# LT1013.net
KiCad netlist of a schematic drawn in EAGLE
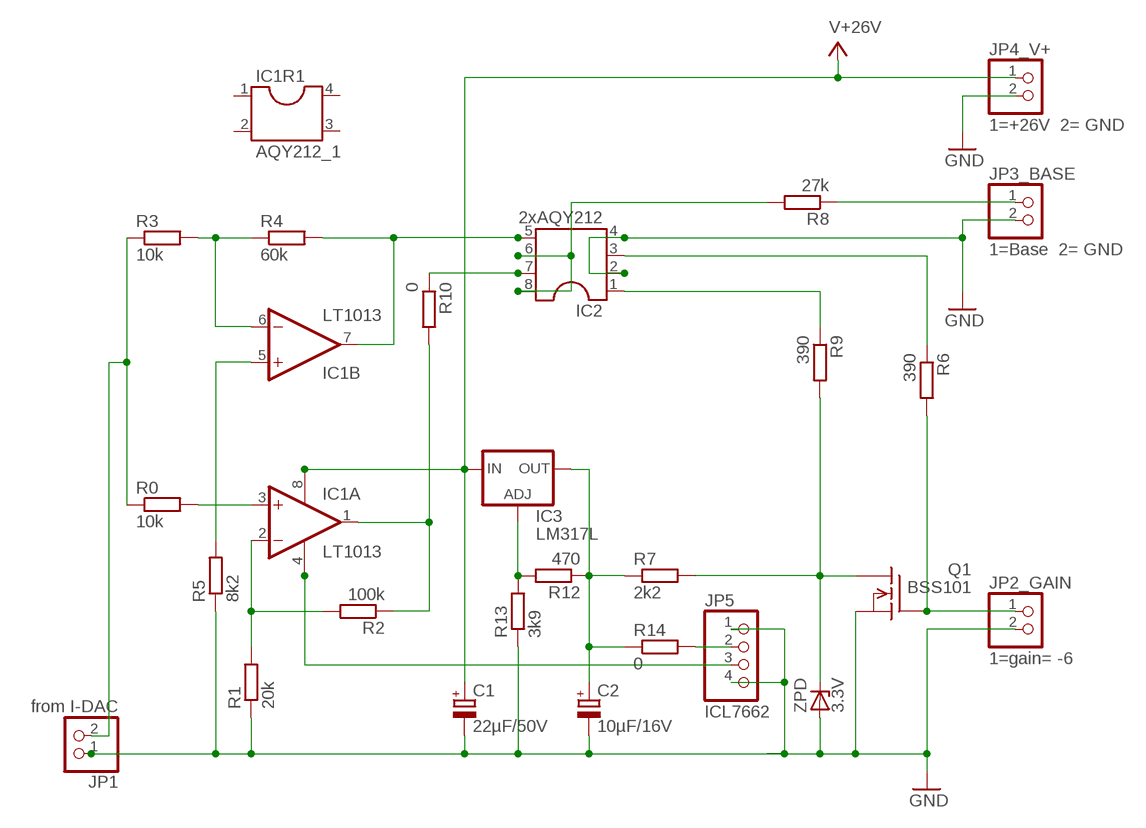
[diagram p0: schematic, sheet 1]

(export (version "E")
  (design (tool "Eeschema 10.0.6"))
  (components
    (comp (ref "C1")
      (value "22µF/50V")
      (footprint "eagle-import:E5-10,5")
      (libsource (lib "eagle-import") (part "CPOL-EUE5-10.5"))
    )
    (comp (ref "C2")
      (value "10µF/16V")
      (footprint "eagle-import:B45181B")
      (libsource (lib "eagle-import") (part "resistor_348_CPOL-EUB45181B"))
    )
    (comp (ref "IC1")
      (value "LT1013")
      (footprint "eagle-import:DIL08")
      (libsource (lib "eagle-import") (part "LF412N"))
    )
    (comp (ref "IC1R1")
      (value "AQY212_1")
      (footprint "eagle-import:SOCKET-04")
      (libsource (lib "eagle-import") (part "DIL4S"))
    )
    (comp (ref "IC2")
      (value "2xAQY212")
      (footprint "eagle-import:SOCKET-08")
      (libsource (lib "eagle-import") (part "DIL8S"))
    )
    (comp (ref "IC3")
      (value "LM317L")
      (footprint "eagle-import:317L")
      (libsource (lib "eagle-import") (part "LM317L"))
    )
    (comp (ref "JP1")
      (value "from I-DAC")
      (footprint "eagle-import:1X02")
      (libsource (lib "eagle-import") (part "PINHD-1X2"))
    )
    (comp (ref "JP2_GAIN")
      (value "1=gain= -6")
      (footprint "eagle-import:1X02")
      (libsource (lib "eagle-import") (part "PINHD-1X2"))
    )
    (comp (ref "JP3_BASE")
      (value "1=Base 2= GND")
      (footprint "eagle-import:1X02")
      (libsource (lib "eagle-import") (part "PINHD-1X2"))
    )
    (comp (ref "JP4_V+")
      (value "1=+26V 2= GND")
      (footprint "eagle-import:1X02")
      (libsource (lib "eagle-import") (part "PINHD-1X2"))
    )
    (comp (ref "JP5")
      (value "ICL7662")
      (footprint "eagle-import:1X04")
      (libsource (lib "eagle-import") (part "PINHD-1X4"))
    )
    (comp (ref "Q1")
      (value "BSS101")
      (footprint "eagle-import:TO92")
      (libsource (lib "eagle-import") (part "BSS101"))
    )
    (comp (ref "R0")
      (value "10k")
      (footprint "eagle-import:0207_7")
      (libsource (lib "eagle-import") (part "R-EU_0207/7"))
    )
    (comp (ref "R1")
      (value "20k")
      (footprint "eagle-import:0207_7")
      (libsource (lib "eagle-import") (part "R-EU_0207/7"))
    )
    (comp (ref "R2")
      (value "100k")
      (footprint "eagle-import:0207_7")
      (libsource (lib "eagle-import") (part "R-EU_0207/7"))
    )
    (comp (ref "R3")
      (value "10k")
      (footprint "eagle-import:0207_7")
      (libsource (lib "eagle-import") (part "R-EU_0207/7"))
    )
    (comp (ref "R4")
      (value "60k")
      (footprint "eagle-import:0207_7")
      (libsource (lib "eagle-import") (part "R-EU_0207/7"))
    )
    (comp (ref "R5")
      (value "8k2")
      (footprint "eagle-import:0207_7")
      (libsource (lib "eagle-import") (part "R-EU_0207/7"))
    )
    (comp (ref "R6")
      (value "390")
      (footprint "eagle-import:0207_7")
      (libsource (lib "eagle-import") (part "R-EU_0207/7"))
    )
    (comp (ref "R7")
      (value "2k2")
      (footprint "eagle-import:0207_7")
      (libsource (lib "eagle-import") (part "R-EU_0207/7"))
    )
    (comp (ref "R8")
      (value "27k")
      (footprint "eagle-import:0207_7")
      (libsource (lib "eagle-import") (part "R-EU_0207/7"))
    )
    (comp (ref "R9")
      (value "390")
      (footprint "eagle-import:0207_7")
      (libsource (lib "eagle-import") (part "R-EU_0207/7"))
    )
    (comp (ref "R10")
      (value "0")
      (footprint "eagle-import:0207_7")
      (libsource (lib "eagle-import") (part "R-EU_0207/7"))
    )
    (comp (ref "R12")
      (value "470")
      (footprint "eagle-import:0207_7")
      (libsource (lib "eagle-import") (part "R-EU_0207/7"))
    )
    (comp (ref "R13")
      (value "3k9")
      (footprint "eagle-import:0207_7")
      (libsource (lib "eagle-import") (part "R-EU_0207/7"))
    )
    (comp (ref "R14")
      (value "0")
      (footprint "eagle-import:0207_7")
      (libsource (lib "eagle-import") (part "R-EU_0207/7"))
    )
    (comp (ref "ZPD")
      (value "3.3V")
      (footprint "eagle-import:ZDIO-7.5")
      (libsource (lib "eagle-import") (part "ZENER-DIODEZD-7.5"))
    )
  )
  (nets
    (net (code "1") (name "GND") (class "Default")
      (node (ref "C1") (pin "-") (pinfunction "-_-") (pintype "passive"))
      (node (ref "C2") (pin "-") (pinfunction "-_-") (pintype "passive"))
      (node (ref "IC2") (pin "2") (pinfunction "2_2") (pintype "passive"))
      (node (ref "IC2") (pin "4") (pinfunction "4_4") (pintype "passive"))
      (node (ref "JP1") (pin "1") (pinfunction "1_1") (pintype "passive"))
      (node (ref "JP2_GAIN") (pin "2") (pinfunction "2_2") (pintype "passive"))
      (node (ref "JP3_BASE") (pin "2") (pinfunction "2_2") (pintype "passive"))
      (node (ref "JP4_V+") (pin "2") (pinfunction "2_2") (pintype "passive"))
      (node (ref "JP5") (pin "1") (pinfunction "1_1") (pintype "passive"))
      (node (ref "JP5") (pin "4") (pinfunction "4_4") (pintype "passive"))
      (node (ref "Q1") (pin "1") (pinfunction "S_1") (pintype "passive"))
      (node (ref "R1") (pin "1") (pinfunction "1_1") (pintype "passive"))
      (node (ref "R13") (pin "1") (pinfunction "1_1") (pintype "passive"))
      (node (ref "R5") (pin "1") (pinfunction "1_1") (pintype "passive"))
      (node (ref "ZPD") (pin "A") (pinfunction "A_A") (pintype "passive"))
    )
    (net (code "2") (name "Net-(IC1A-+IN)") (class "Default")
      (node (ref "IC1") (pin "3") (pinfunction "+IN_3") (pintype "input"))
      (node (ref "R0") (pin "2") (pinfunction "2_2") (pintype "passive"))
    )
    (net (code "3") (name "Net-(IC1A--IN)") (class "Default")
      (node (ref "IC1") (pin "2") (pinfunction "-IN_2") (pintype "input"))
      (node (ref "R1") (pin "2") (pinfunction "2_2") (pintype "passive"))
      (node (ref "R2") (pin "2") (pinfunction "2_2") (pintype "passive"))
    )
    (net (code "4") (name "Net-(IC1A-OUT)") (class "Default")
      (node (ref "IC1") (pin "1") (pinfunction "OUT_1") (pintype "output"))
      (node (ref "R10") (pin "2") (pinfunction "2_2") (pintype "passive"))
      (node (ref "R2") (pin "1") (pinfunction "1_1") (pintype "passive"))
    )
    (net (code "5") (name "Net-(IC1B-+IN)") (class "Default")
      (node (ref "IC1") (pin "5") (pinfunction "+IN_5") (pintype "input"))
      (node (ref "R5") (pin "2") (pinfunction "2_2") (pintype "passive"))
    )
    (net (code "6") (name "Net-(IC1B--IN)") (class "Default")
      (node (ref "IC1") (pin "6") (pinfunction "-IN_6") (pintype "input"))
      (node (ref "R3") (pin "2") (pinfunction "2_2") (pintype "passive"))
      (node (ref "R4") (pin "1") (pinfunction "1_1") (pintype "passive"))
    )
    (net (code "7") (name "Net-(IC1B-OUT)") (class "Default")
      (node (ref "IC1") (pin "7") (pinfunction "OUT_7") (pintype "output"))
      (node (ref "IC2") (pin "5") (pinfunction "5_5") (pintype "passive"))
      (node (ref "R4") (pin "2") (pinfunction "2_2") (pintype "passive"))
    )
    (net (code "8") (name "Net-(IC1C-V-)") (class "Default")
      (node (ref "IC1") (pin "4") (pinfunction "V-_4") (pintype "power_in"))
      (node (ref "JP5") (pin "3") (pinfunction "3_3") (pintype "passive"))
    )
    (net (code "9") (name "Net-(IC2-Pad1)") (class "Default")
      (node (ref "IC2") (pin "1") (pinfunction "1_1") (pintype "passive"))
      (node (ref "R9") (pin "1") (pinfunction "1_1") (pintype "passive"))
    )
    (net (code "10") (name "Net-(IC2-Pad3)") (class "Default")
      (node (ref "IC2") (pin "3") (pinfunction "3_3") (pintype "passive"))
      (node (ref "R6") (pin "1") (pinfunction "1_1") (pintype "passive"))
    )
    (net (code "11") (name "Net-(IC2-Pad6)") (class "Default")
      (node (ref "IC2") (pin "6") (pinfunction "6_6") (pintype "passive"))
      (node (ref "IC2") (pin "8") (pinfunction "8_8") (pintype "passive"))
      (node (ref "R8") (pin "2") (pinfunction "2_2") (pintype "passive"))
    )
    (net (code "12") (name "Net-(IC2-Pad7)") (class "Default")
      (node (ref "IC2") (pin "7") (pinfunction "7_7") (pintype "passive"))
      (node (ref "R10") (pin "1") (pinfunction "1_1") (pintype "passive"))
    )
    (net (code "13") (name "Net-(IC3-ADJ)") (class "Default")
      (node (ref "IC3") (pin "1") (pinfunction "ADJ_1") (pintype "input"))
      (node (ref "R12") (pin "2") (pinfunction "2_2") (pintype "passive"))
      (node (ref "R13") (pin "2") (pinfunction "2_2") (pintype "passive"))
    )
    (net (code "14") (name "Net-(IC3-OUT)") (class "Default")
      (node (ref "C2") (pin "+") (pinfunction "+_+") (pintype "passive"))
      (node (ref "IC3") (pin "2") (pinfunction "OUT_2") (pintype "passive"))
      (node (ref "R12") (pin "1") (pinfunction "1_1") (pintype "passive"))
      (node (ref "R14") (pin "1") (pinfunction "1_1") (pintype "passive"))
      (node (ref "R7") (pin "1") (pinfunction "1_1") (pintype "passive"))
    )
    (net (code "15") (name "Net-(JP1-Pad2)") (class "Default")
      (node (ref "JP1") (pin "2") (pinfunction "2_2") (pintype "passive"))
      (node (ref "R0") (pin "1") (pinfunction "1_1") (pintype "passive"))
      (node (ref "R3") (pin "1") (pinfunction "1_1") (pintype "passive"))
    )
    (net (code "16") (name "Net-(JP3_BASE-Pad1)") (class "Default")
      (node (ref "JP3_BASE") (pin "1") (pinfunction "1_1") (pintype "passive"))
      (node (ref "R8") (pin "1") (pinfunction "1_1") (pintype "passive"))
    )
    (net (code "17") (name "Net-(JP5-Pad2)") (class "Default")
      (node (ref "JP5") (pin "2") (pinfunction "2_2") (pintype "passive"))
      (node (ref "R14") (pin "2") (pinfunction "2_2") (pintype "passive"))
    )
    (net (code "18") (name "Net-(Q1-D)") (class "Default")
      (node (ref "Q1") (pin "3") (pinfunction "D_3") (pintype "passive"))
      (node (ref "R7") (pin "2") (pinfunction "2_2") (pintype "passive"))
      (node (ref "R9") (pin "2") (pinfunction "2_2") (pintype "passive"))
      (node (ref "ZPD") (pin "C") (pinfunction "C_C") (pintype "passive"))
    )
    (net (code "19") (name "Net-(Q1-G)") (class "Default")
      (node (ref "JP2_GAIN") (pin "1") (pinfunction "1_1") (pintype "passive"))
      (node (ref "Q1") (pin "2") (pinfunction "G_2") (pintype "passive"))
      (node (ref "R6") (pin "2") (pinfunction "2_2") (pintype "passive"))
    )
    (net (code "20") (name "V+26V") (class "Default")
      (node (ref "C1") (pin "+") (pinfunction "+_+") (pintype "passive"))
      (node (ref "IC1") (pin "8") (pinfunction "V+_8") (pintype "power_in"))
      (node (ref "IC3") (pin "3") (pinfunction "IN_3") (pintype "input"))
      (node (ref "JP4_V+") (pin "1") (pinfunction "1_1") (pintype "passive"))
    )
    (net (code "21") (name "unconnected-(IC1R1-Pad1)") (class "Default")
      (node (ref "IC1R1") (pin "1") (pinfunction "1_1") (pintype "passive"))
    )
    (net (code "22") (name "unconnected-(IC1R1-Pad2)") (class "Default")
      (node (ref "IC1R1") (pin "2") (pinfunction "2_2") (pintype "passive"))
    )
    (net (code "23") (name "unconnected-(IC1R1-Pad3)") (class "Default")
      (node (ref "IC1R1") (pin "3") (pinfunction "3_3") (pintype "passive"))
    )
    (net (code "24") (name "unconnected-(IC1R1-Pad4)") (class "Default")
      (node (ref "IC1R1") (pin "4") (pinfunction "4_4") (pintype "passive"))
    )
  )
)
